# weather_baloon_tx.net
KiCad netlist of a schematic drawn in EAGLE
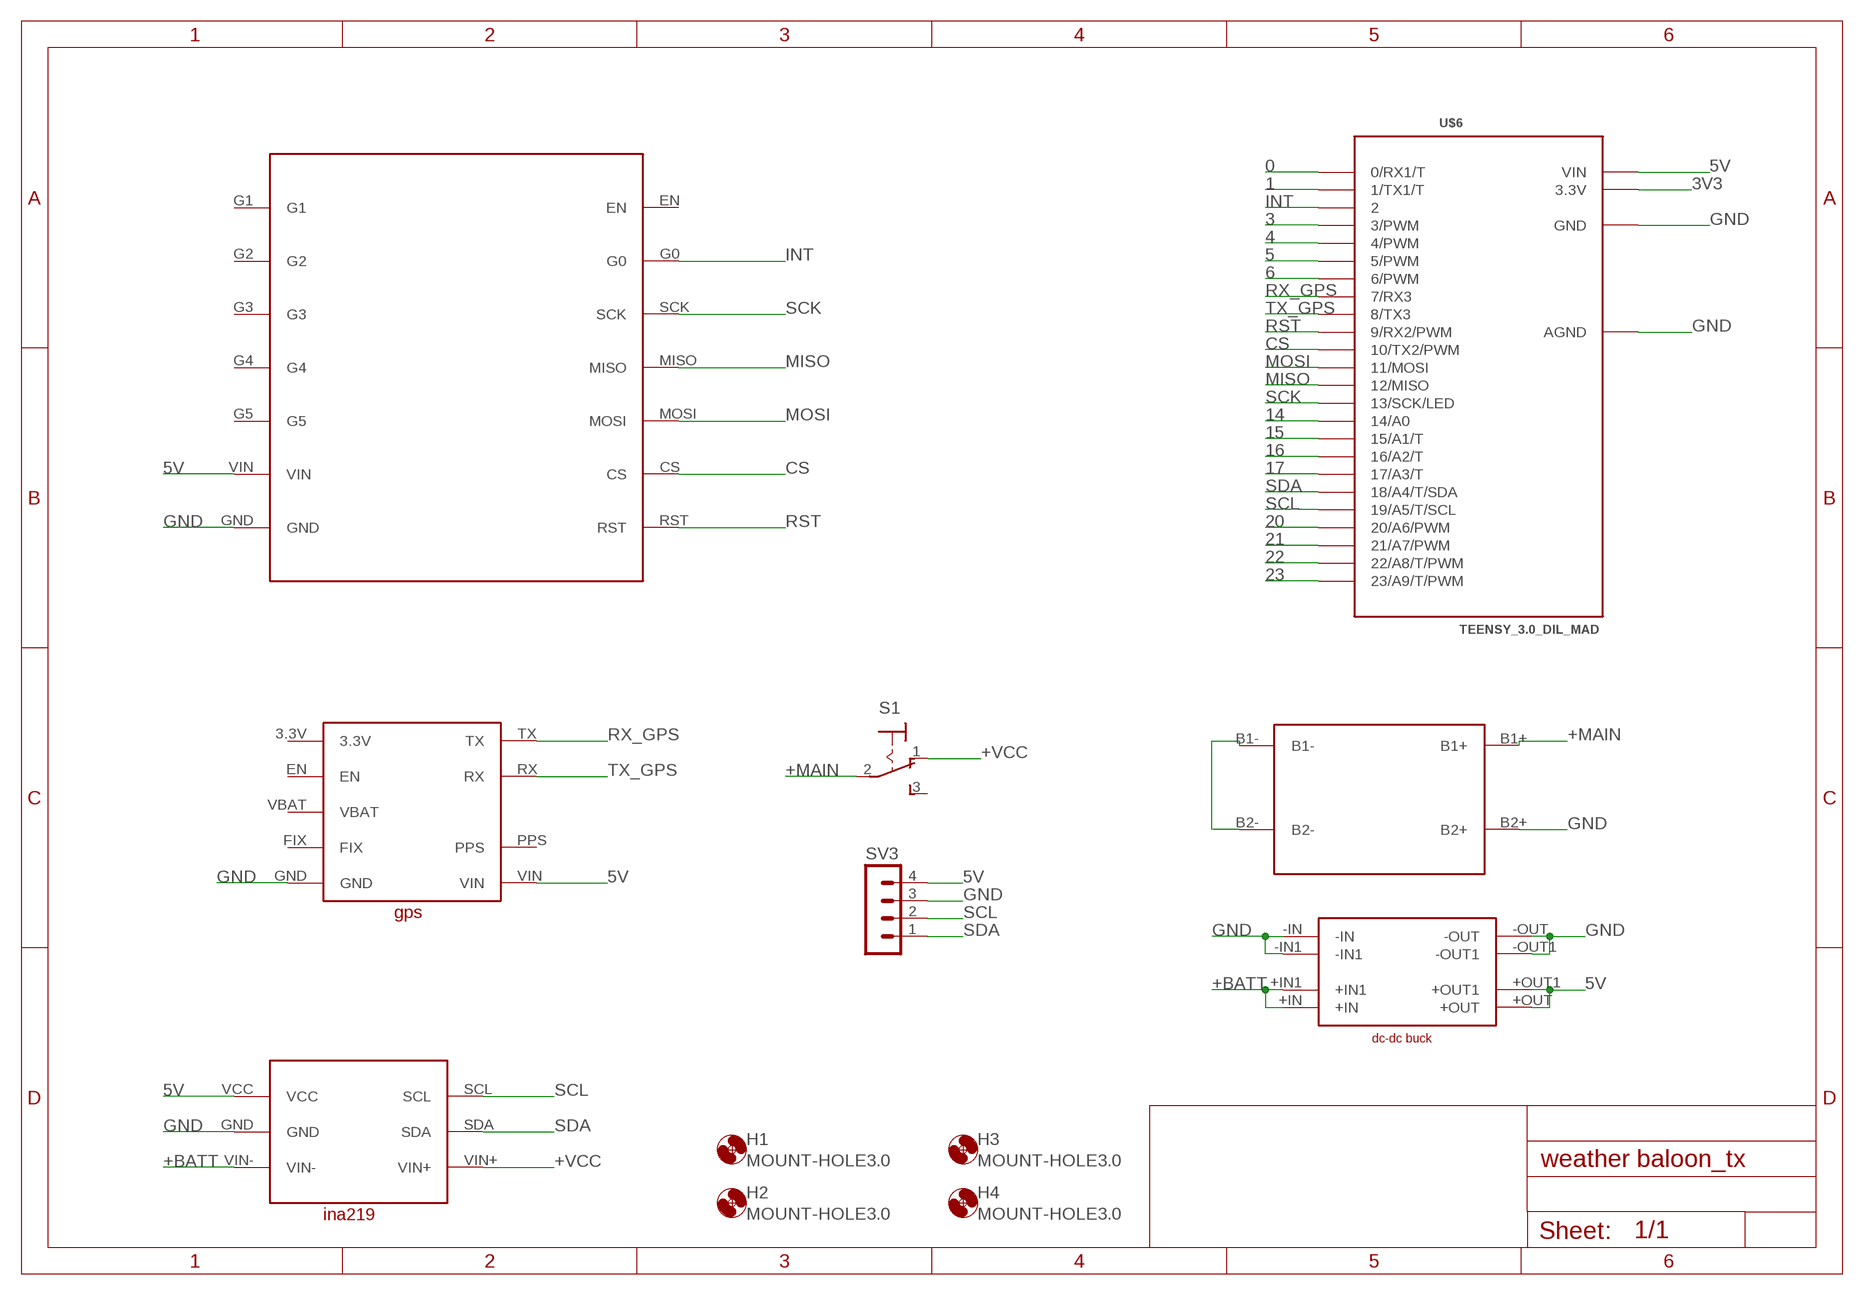
[diagram p0: schematic, sheet 1]

(export (version "E")
  (design (tool "Eeschema 10.0.6"))
  (components
    (comp (ref "H1")
      (value "MOUNT-HOLE3.0")
      (footprint "eagle-import:3,0")
      (libsource (lib "eagle-import") (part "MOUNT-HOLE3.0"))
    )
    (comp (ref "H2")
      (value "MOUNT-HOLE3.0")
      (footprint "eagle-import:3,0")
      (libsource (lib "eagle-import") (part "MOUNT-HOLE3.0"))
    )
    (comp (ref "H3")
      (value "MOUNT-HOLE3.0")
      (footprint "eagle-import:3,0")
      (libsource (lib "eagle-import") (part "MOUNT-HOLE3.0"))
    )
    (comp (ref "H4")
      (value "MOUNT-HOLE3.0")
      (footprint "eagle-import:3,0")
      (libsource (lib "eagle-import") (part "MOUNT-HOLE3.0"))
    )
    (comp (ref "S1")
      (value "320-916")
      (footprint "eagle-import:320-916")
      (libsource (lib "eagle-import") (part "320-916"))
    )
    (comp (ref "SV3")
      (value "MA04-1")
      (footprint "eagle-import:MA04-1")
      (libsource (lib "eagle-import") (part "MA04-1"))
    )
    (comp (ref "U$1")
      (value "RFM96_MAD")
      (footprint "eagle-import:RFM96")
      (libsource (lib "eagle-import") (part "RFM96_MAD"))
    )
    (comp (ref "U$2")
      (value "DC-DC_BUCK_MAD")
      (footprint "eagle-import:DC-DC_BUCK")
      (libsource (lib "eagle-import") (part "DC-DC_BUCK_MAD"))
    )
    (comp (ref "U$3")
      (value "GPS_MAD")
      (footprint "eagle-import:GPS")
      (libsource (lib "eagle-import") (part "GPS_MAD"))
    )
    (comp (ref "U$4")
      (value "18650-2")
      (footprint "eagle-import:18650-2")
      (libsource (lib "eagle-import") (part "18650-2"))
    )
    (comp (ref "U$5")
      (value "INA219_MAD")
      (footprint "eagle-import:INA219")
      (libsource (lib "eagle-import") (part "INA219_MAD"))
    )
    (comp (ref "U$6")
      (value "TEENSY_3.0_DIL_MAD")
      (footprint "eagle-import:TEENSY_3.0_DIL_MAD")
      (libsource (lib "eagle-import") (part "TEENSY_3.0_DIL_MAD"))
    )
  )
  (nets
    (net (code "1") (name "/+BATT") (class "Default")
      (node (ref "U$2") (pin "+IN") (pinfunction "+IN_+IN") (pintype "bidirectional"))
      (node (ref "U$2") (pin "+IN1") (pinfunction "+IN1_+IN1") (pintype "bidirectional"))
      (node (ref "U$5") (pin "VIN-") (pinfunction "VIN-_VIN-") (pintype "bidirectional"))
    )
    (net (code "2") (name "/+MAIN") (class "Default")
      (node (ref "S1") (pin "2") (pinfunction "P_2") (pintype "passive"))
      (node (ref "U$4") (pin "B1+") (pinfunction "B1+_B1+") (pintype "bidirectional"))
    )
    (net (code "3") (name "/+VCC") (class "Default")
      (node (ref "S1") (pin "1") (pinfunction "O_1") (pintype "passive"))
      (node (ref "U$5") (pin "VIN+") (pinfunction "VIN+_VIN+") (pintype "bidirectional"))
    )
    (net (code "4") (name "/0") (class "Default")
      (node (ref "U$6") (pin "0") (pinfunction "0/RX1/T_0") (pintype "bidirectional"))
    )
    (net (code "5") (name "/1") (class "Default")
      (node (ref "U$6") (pin "1") (pinfunction "1/TX1/T_1") (pintype "bidirectional"))
    )
    (net (code "6") (name "/3") (class "Default")
      (node (ref "U$6") (pin "3") (pinfunction "3/PWM_3") (pintype "bidirectional"))
    )
    (net (code "7") (name "/3V3") (class "Default")
      (node (ref "U$6") (pin "3.3V") (pinfunction "3.3V_3.3V") (pintype "power_in"))
    )
    (net (code "8") (name "/4") (class "Default")
      (node (ref "U$6") (pin "4") (pinfunction "4/PWM_4") (pintype "bidirectional"))
    )
    (net (code "9") (name "/5") (class "Default")
      (node (ref "U$6") (pin "5") (pinfunction "5/PWM_5") (pintype "bidirectional"))
    )
    (net (code "10") (name "/5V") (class "Default")
      (node (ref "SV3") (pin "4") (pinfunction "4_4") (pintype "passive"))
      (node (ref "U$1") (pin "VIN") (pinfunction "VIN_VIN") (pintype "bidirectional"))
      (node (ref "U$2") (pin "+OUT") (pinfunction "+OUT_+OUT") (pintype "bidirectional"))
      (node (ref "U$2") (pin "+OUT1") (pinfunction "+OUT1_+OUT1") (pintype "bidirectional"))
      (node (ref "U$3") (pin "VIN") (pinfunction "VIN_VIN") (pintype "bidirectional"))
      (node (ref "U$5") (pin "VCC") (pinfunction "VCC_VCC") (pintype "bidirectional"))
      (node (ref "U$6") (pin "VIN") (pinfunction "VIN_VIN") (pintype "power_in"))
    )
    (net (code "11") (name "/6") (class "Default")
      (node (ref "U$6") (pin "6") (pinfunction "6/PWM_6") (pintype "bidirectional"))
    )
    (net (code "12") (name "/14") (class "Default")
      (node (ref "U$6") (pin "14/A0") (pinfunction "14/A0_14/A0") (pintype "bidirectional"))
    )
    (net (code "13") (name "/15") (class "Default")
      (node (ref "U$6") (pin "15/A1") (pinfunction "15/A1/T_15/A1") (pintype "bidirectional"))
    )
    (net (code "14") (name "/16") (class "Default")
      (node (ref "U$6") (pin "16/A2") (pinfunction "16/A2/T_16/A2") (pintype "bidirectional"))
    )
    (net (code "15") (name "/17") (class "Default")
      (node (ref "U$6") (pin "17/A3") (pinfunction "17/A3/T_17/A3") (pintype "bidirectional"))
    )
    (net (code "16") (name "/20") (class "Default")
      (node (ref "U$6") (pin "20/A6") (pinfunction "20/A6/PWM_20/A6") (pintype "bidirectional"))
    )
    (net (code "17") (name "/21") (class "Default")
      (node (ref "U$6") (pin "21/A7") (pinfunction "21/A7/PWM_21/A7") (pintype "bidirectional"))
    )
    (net (code "18") (name "/22") (class "Default")
      (node (ref "U$6") (pin "22/A8") (pinfunction "22/A8/T/PWM_22/A8") (pintype "bidirectional"))
    )
    (net (code "19") (name "/23") (class "Default")
      (node (ref "U$6") (pin "23/A9") (pinfunction "23/A9/T/PWM_23/A9") (pintype "bidirectional"))
    )
    (net (code "20") (name "/CS") (class "Default")
      (node (ref "U$1") (pin "CS") (pinfunction "CS_CS") (pintype "bidirectional"))
      (node (ref "U$6") (pin "10") (pinfunction "10/TX2/PWM_10") (pintype "bidirectional"))
    )
    (net (code "21") (name "/GND") (class "Default")
      (node (ref "SV3") (pin "3") (pinfunction "3_3") (pintype "passive"))
      (node (ref "U$1") (pin "GND") (pinfunction "GND_GND") (pintype "bidirectional"))
      (node (ref "U$2") (pin "-IN") (pinfunction "-IN_-IN") (pintype "bidirectional"))
      (node (ref "U$2") (pin "-IN1") (pinfunction "-IN1_-IN1") (pintype "bidirectional"))
      (node (ref "U$2") (pin "-OUT") (pinfunction "-OUT_-OUT") (pintype "bidirectional"))
      (node (ref "U$2") (pin "-OUT1") (pinfunction "-OUT1_-OUT1") (pintype "bidirectional"))
      (node (ref "U$3") (pin "GND") (pinfunction "GND_GND") (pintype "bidirectional"))
      (node (ref "U$4") (pin "B2+") (pinfunction "B2+_B2+") (pintype "bidirectional"))
      (node (ref "U$5") (pin "GND") (pinfunction "GND_GND") (pintype "bidirectional"))
      (node (ref "U$6") (pin "AGND") (pinfunction "AGND_AGND") (pintype "power_in"))
      (node (ref "U$6") (pin "GND") (pinfunction "GND_GND") (pintype "power_in"))
    )
    (net (code "22") (name "/INT") (class "Default")
      (node (ref "U$1") (pin "G0") (pinfunction "G0_G0") (pintype "bidirectional"))
      (node (ref "U$6") (pin "2") (pinfunction "2_2") (pintype "bidirectional"))
    )
    (net (code "23") (name "/MISO") (class "Default")
      (node (ref "U$1") (pin "MISO") (pinfunction "MISO_MISO") (pintype "bidirectional"))
      (node (ref "U$6") (pin "12") (pinfunction "12/MISO_12") (pintype "bidirectional"))
    )
    (net (code "24") (name "/MOSI") (class "Default")
      (node (ref "U$1") (pin "MOSI") (pinfunction "MOSI_MOSI") (pintype "bidirectional"))
      (node (ref "U$6") (pin "11") (pinfunction "11/MOSI_11") (pintype "bidirectional"))
    )
    (net (code "25") (name "/RST") (class "Default")
      (node (ref "U$1") (pin "RST") (pinfunction "RST_RST") (pintype "bidirectional"))
      (node (ref "U$6") (pin "9") (pinfunction "9/RX2/PWM_9") (pintype "bidirectional"))
    )
    (net (code "26") (name "/RX_GPS") (class "Default")
      (node (ref "U$3") (pin "TX") (pinfunction "TX_TX") (pintype "bidirectional"))
      (node (ref "U$6") (pin "7") (pinfunction "7/RX3_7") (pintype "bidirectional"))
    )
    (net (code "27") (name "/SCK") (class "Default")
      (node (ref "U$1") (pin "SCK") (pinfunction "SCK_SCK") (pintype "bidirectional"))
      (node (ref "U$6") (pin "13") (pinfunction "13/SCK/LED_13") (pintype "bidirectional"))
    )
    (net (code "28") (name "/SCL") (class "Default")
      (node (ref "SV3") (pin "2") (pinfunction "2_2") (pintype "passive"))
      (node (ref "U$5") (pin "SCL") (pinfunction "SCL_SCL") (pintype "bidirectional"))
      (node (ref "U$6") (pin "19/A5") (pinfunction "19/A5/T/SCL_19/A5") (pintype "bidirectional"))
    )
    (net (code "29") (name "/SDA") (class "Default")
      (node (ref "SV3") (pin "1") (pinfunction "1_1") (pintype "passive"))
      (node (ref "U$5") (pin "SDA") (pinfunction "SDA_SDA") (pintype "bidirectional"))
      (node (ref "U$6") (pin "18/A4") (pinfunction "18/A4/T/SDA_18/A4") (pintype "bidirectional"))
    )
    (net (code "30") (name "/TX_GPS") (class "Default")
      (node (ref "U$3") (pin "RX") (pinfunction "RX_RX") (pintype "bidirectional"))
      (node (ref "U$6") (pin "8") (pinfunction "8/TX3_8") (pintype "bidirectional"))
    )
    (net (code "31") (name "Net-(U$4-PadB1-)") (class "Default")
      (node (ref "U$4") (pin "B1-") (pinfunction "B1-_B1-") (pintype "bidirectional"))
      (node (ref "U$4") (pin "B2-") (pinfunction "B2-_B2-") (pintype "bidirectional"))
    )
    (net (code "32") (name "unconnected-(S1-S-Pad3)") (class "Default")
      (node (ref "S1") (pin "3") (pinfunction "S_3") (pintype "passive"))
    )
    (net (code "33") (name "unconnected-(U$1-PadEN)") (class "Default")
      (node (ref "U$1") (pin "EN") (pinfunction "EN_EN") (pintype "bidirectional"))
    )
    (net (code "34") (name "unconnected-(U$1-PadG1)") (class "Default")
      (node (ref "U$1") (pin "G1") (pinfunction "G1_G1") (pintype "bidirectional"))
    )
    (net (code "35") (name "unconnected-(U$1-PadG2)") (class "Default")
      (node (ref "U$1") (pin "G2") (pinfunction "G2_G2") (pintype "bidirectional"))
    )
    (net (code "36") (name "unconnected-(U$1-PadG3)") (class "Default")
      (node (ref "U$1") (pin "G3") (pinfunction "G3_G3") (pintype "bidirectional"))
    )
    (net (code "37") (name "unconnected-(U$1-PadG4)") (class "Default")
      (node (ref "U$1") (pin "G4") (pinfunction "G4_G4") (pintype "bidirectional"))
    )
    (net (code "38") (name "unconnected-(U$1-PadG5)") (class "Default")
      (node (ref "U$1") (pin "G5") (pinfunction "G5_G5") (pintype "bidirectional"))
    )
    (net (code "39") (name "unconnected-(U$3-Pad3.3V)") (class "Default")
      (node (ref "U$3") (pin "3.3V") (pinfunction "3.3V_3.3V") (pintype "bidirectional"))
    )
    (net (code "40") (name "unconnected-(U$3-PadEN)") (class "Default")
      (node (ref "U$3") (pin "EN") (pinfunction "EN_EN") (pintype "bidirectional"))
    )
    (net (code "41") (name "unconnected-(U$3-PadFIX)") (class "Default")
      (node (ref "U$3") (pin "FIX") (pinfunction "FIX_FIX") (pintype "bidirectional"))
    )
    (net (code "42") (name "unconnected-(U$3-PadPPS)") (class "Default")
      (node (ref "U$3") (pin "PPS") (pinfunction "PPS_PPS") (pintype "bidirectional"))
    )
    (net (code "43") (name "unconnected-(U$3-PadVBAT)") (class "Default")
      (node (ref "U$3") (pin "VBAT") (pinfunction "VBAT_VBAT") (pintype "bidirectional"))
    )
  )
)
